# RELAYS.net
KiCad netlist of a schematic drawn in Altium Designer
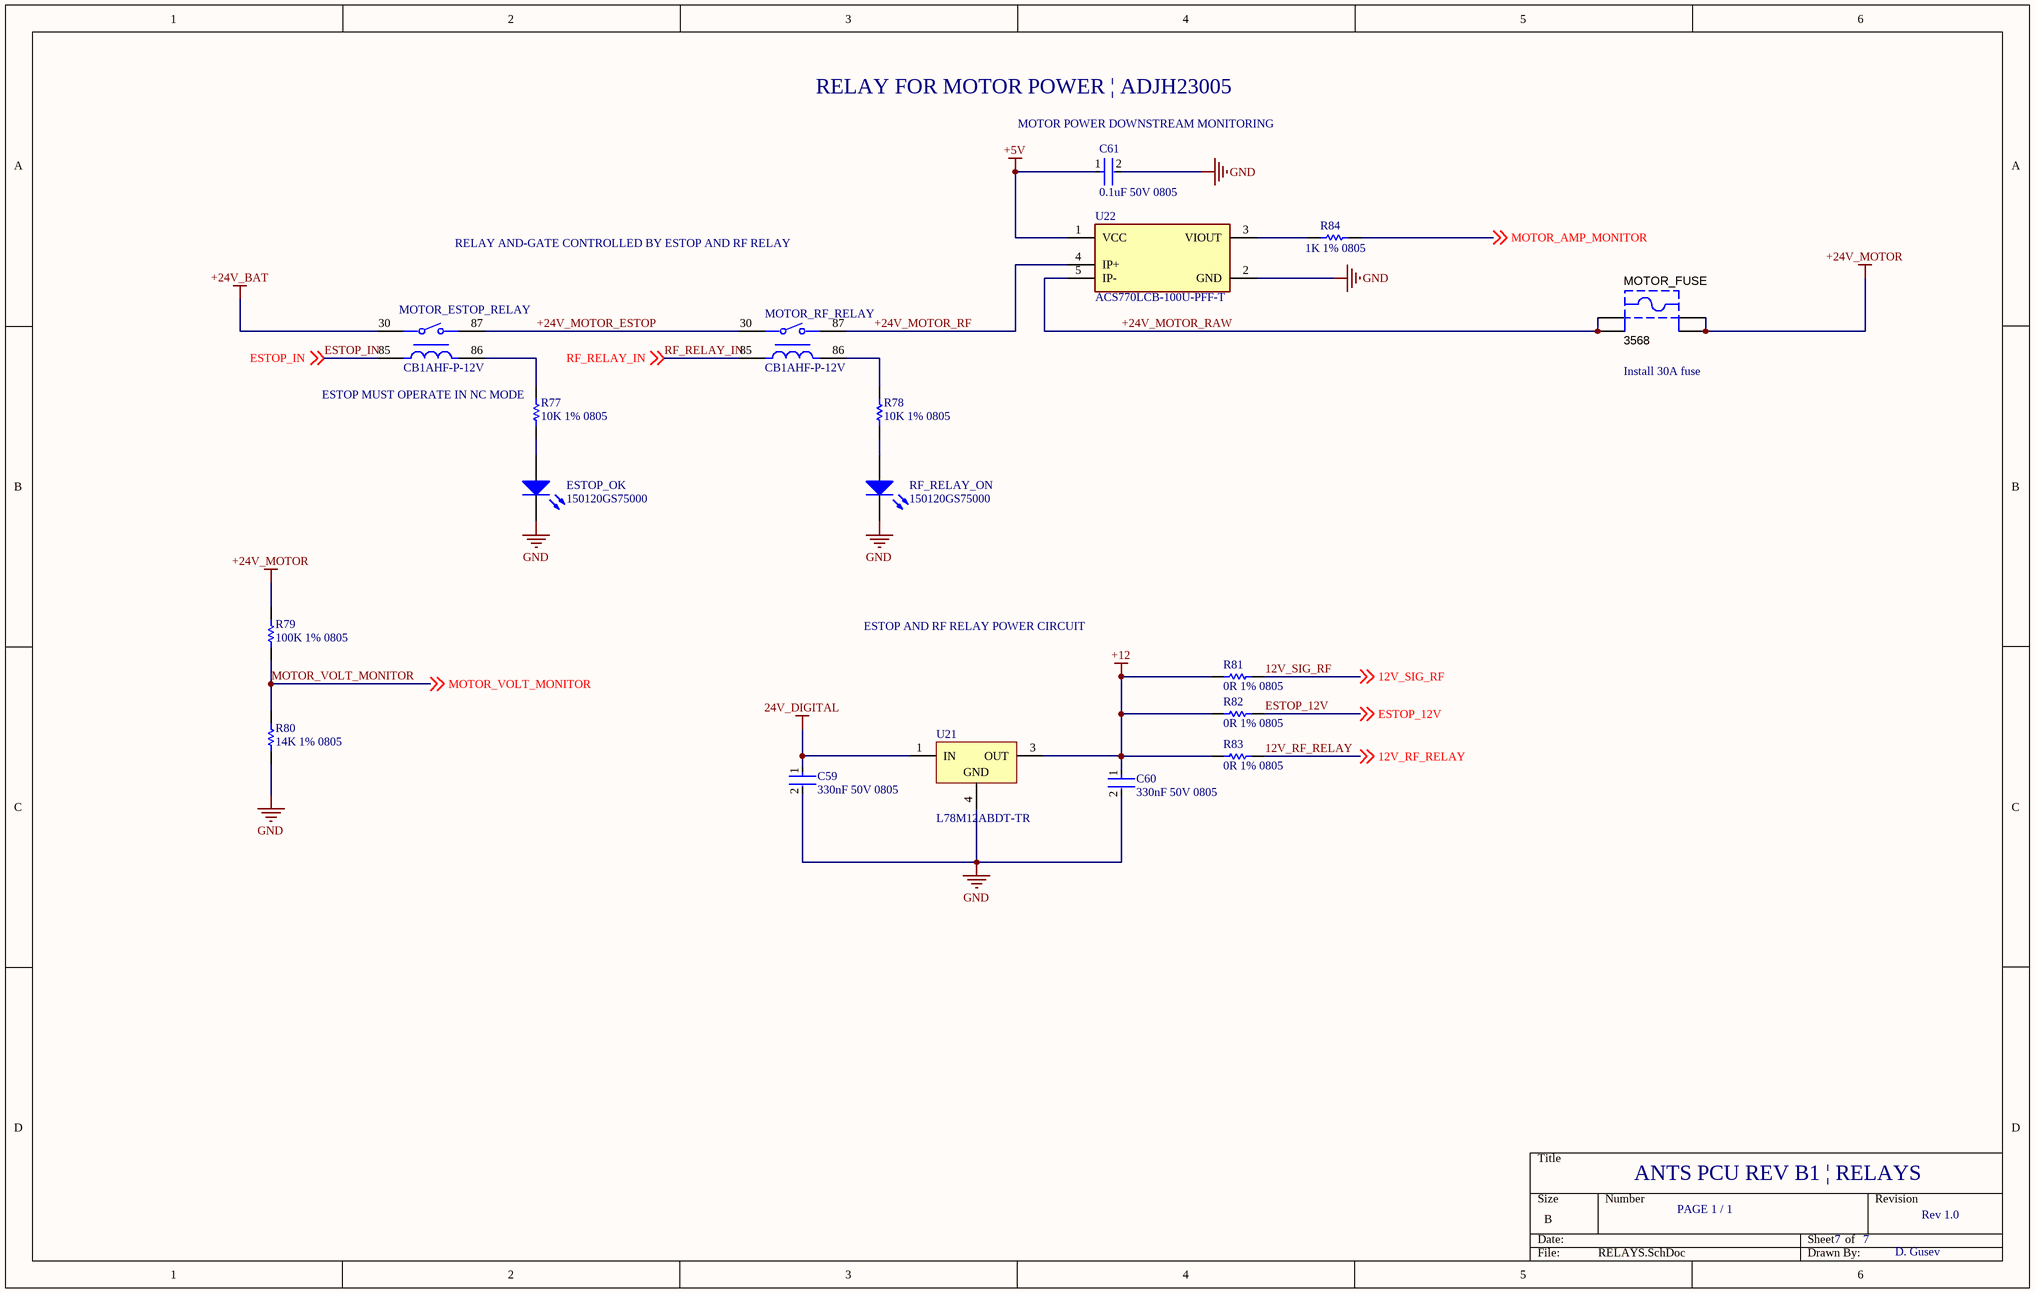
[diagram p0: RELAYS.SchDoc]

(export (version "E")
  (design (tool "Eeschema 10.0.6"))
  (components
    (comp (ref "C59")
      (value "330nF 50V 0805")
      (footprint "FP-C0805C-DN-MFG")
      (description "CAP CER 0.33UF 50V X7R 0805")
      (fields
        (field (name "MANUFACTURER PART NUMBER") "C0805C334K5RACTU")
        (field (name "MANUFACTURER") "KEMET")
      )
      (libsource (lib "Altium Content Vault") (part "b4654b650e69147ec39a6b967a45e02"))
    )
    (comp (ref "C60")
      (value "330nF 50V 0805")
      (footprint "FP-C0805C-DN-MFG")
      (description "CAP CER 0.33UF 50V X7R 0805")
      (fields
        (field (name "MANUFACTURER PART NUMBER") "C0805C334K5RACTU")
        (field (name "MANUFACTURER") "KEMET")
      )
      (libsource (lib "Altium Content Vault") (part "b4654b650e69147ec39a6b967a45e02"))
    )
    (comp (ref "C61")
      (value "0.1uF 50V 0805")
      (footprint "FP-C0805C-DN-MFG")
      (description "CAP CER 0.1UF 50V X7R 0805")
      (fields
        (field (name "MANUFACTURER PART NUMBER") "C0805C104K5RACTU")
        (field (name "MANUFACTURER") "KEMET")
      )
      (libsource (lib "Altium Content Vault") (part "b4654b650e69147ec39a6b967a45e02"))
    )
    (comp (ref "ESTOP_OK")
      (value "150120GS75000")
      (footprint "1206_A")
      (description "SMD mono-color Chip LED, WL-SMCW, Green")
      (fields (field (name "MANUFACTURER") "Wuerth Elektronik"))
      (libsource (lib "Altium Content Vault") (part "WE-LED_K1A2-2"))
    )
    (comp (ref "MOTOR_ESTOP_RELAY")
      (value "CB1AHF-P-12V")
      (footprint "FP-CB1AHF-P-12V-MFG")
      (description "RELAY AUTOMOTIVE SPST 70A 12V")
      (libsource (lib "Altium Content Vault") (part "118a8ddf33a3f36f50d1a42db1624c5"))
    )
    (comp (ref "MOTOR_FUSE")
      (value "3568")
      (footprint "KSTN-3568_V")
      (description "Fuse Holder, 20 A, 500 V, -50 to 145 degC, 4-Pin THD, RoHS")
      (fields (field (name "MANUFACTURER") "Keystone"))
      (libsource (lib "Altium Content Vault") (part "FUSE_HOLDER-4"))
    )
    (comp (ref "MOTOR_RF_RELAY")
      (value "CB1AHF-P-12V")
      (footprint "FP-CB1AHF-P-12V-MFG")
      (description "RELAY AUTOMOTIVE SPST 70A 12V")
      (libsource (lib "Altium Content Vault") (part "118a8ddf33a3f36f50d1a42db1624c5"))
    )
    (comp (ref "R77")
      (value "10K 1% 0805")
      (footprint "RESC2013X60X35NL10T20")
      (description "Chip Resistor, 10 KOhm, +/- 1%, 0.125 W, -55 to 155 degC, 0805 (2012 Metric), RoHS, Tape and Reel")
      (fields (field (name "MANUFACTURER") "Yageo"))
      (libsource (lib "Altium Content Vault") (part "RES-2"))
    )
    (comp (ref "R78")
      (value "10K 1% 0805")
      (footprint "RESC2013X60X35NL10T20")
      (description "Chip Resistor, 10 KOhm, +/- 1%, 0.125 W, -55 to 155 degC, 0805 (2012 Metric), RoHS, Tape and Reel")
      (fields (field (name "MANUFACTURER") "Yageo"))
      (libsource (lib "Altium Content Vault") (part "RES-2"))
    )
    (comp (ref "R79")
      (value "100K 1% 0805")
      (footprint "RESC2013X60X35ML10T20")
      (description "Chip Resistor, 100 KOhm, +/- 1%, 0.125 W, -55 to 155 degC, 0805 (2012 Metric), RoHS, Tape and Reel")
      (fields (field (name "MANUFACTURER") "Yageo") (field (name "TOLERANCE") "1%"))
      (libsource (lib "Altium Content Vault") (part "RES-2"))
    )
    (comp (ref "R80")
      (value "14K 1% 0805")
      (footprint "RESC2013X60X35LL10T20")
      (fields (field (name "PART NUMBER") "RC0805FR-0714KL") (field (name "MANUFACTURER") "Yageo"))
      (libsource (lib "Altium Content Vault") (part "RES"))
    )
    (comp (ref "R81")
      (value "0R 1% 0805")
      (footprint "RESC2013X60X35LL10T20")
      (description "Chip Resistor, 1 Ohm, +/- 1%, 125 mW, -55 to 155 degC, 0805 (2012 Metric), RoHS, Tape and Reel")
      (fields (field (name "MANUFACTURER") "Yageo"))
      (libsource (lib "Altium Content Vault") (part "RES-2"))
    )
    (comp (ref "R82")
      (value "0R 1% 0805")
      (footprint "RESC2013X60X35LL10T20")
      (description "Chip Resistor, 1 Ohm, +/- 1%, 125 mW, -55 to 155 degC, 0805 (2012 Metric), RoHS, Tape and Reel")
      (fields (field (name "MANUFACTURER") "Yageo"))
      (libsource (lib "Altium Content Vault") (part "RES-2"))
    )
    (comp (ref "R83")
      (value "0R 1% 0805")
      (footprint "RESC2013X60X35LL10T20")
      (description "Chip Resistor, 1 Ohm, +/- 1%, 125 mW, -55 to 155 degC, 0805 (2012 Metric), RoHS, Tape and Reel")
      (fields (field (name "MANUFACTURER") "Yageo"))
      (libsource (lib "Altium Content Vault") (part "RES-2"))
    )
    (comp (ref "R84")
      (value "1K 1% 0805")
      (footprint "RESC2013X60X35ML10T20")
      (description "Chip Resistor, 1 KOhm, +/- 1%, 125 mW, -55 to 155 degC, 0805 (2012 Metric), RoHS, Tape and Reel")
      (fields (field (name "TOLERANCE") "1%") (field (name "MANUFACTURER") "Yageo"))
      (libsource (lib "Altium Content Vault") (part "RES-2"))
    )
    (comp (ref "RF_RELAY_ON")
      (value "150120GS75000")
      (footprint "1206_A")
      (description "SMD mono-color Chip LED, WL-SMCW, Green")
      (fields (field (name "MANUFACTURER") "Wuerth Elektronik"))
      (libsource (lib "Altium Content Vault") (part "WE-LED_K1A2-2"))
    )
    (comp (ref "U21")
      (value "L78M12ABDT-TR")
      (footprint "TO-252_M")
      (description "Precision 500mA Regulator, 12V, 3-Pin DPAK, Tape and Reel")
      (libsource (lib "Altium Content Vault") (part "PM-REG-L4940-SOT3"))
    )
    (comp (ref "U22")
      (value "ACS770LCB-100U-PFF-T")
      (footprint "ACS770LCB-100U-PFF-T")
      (description "SENSOR CURRENT HALL 100A DC")
      (libsource (lib "ANTS-PCU-B1") (part "ACS770LCB-100U-PFF-T"))
    )
  )
  (nets
    (net (code "1") (name "+5V") (class "Default")
      (node (ref "C61") (pin "1") (pinfunction "1_1") (pintype "passive"))
      (node (ref "U22") (pin "1") (pinfunction "VCC_1") (pintype "power_in"))
    )
    (net (code "2") (name "+12") (class "Default")
      (node (ref "C60") (pin "1") (pinfunction "1_1") (pintype "passive"))
      (node (ref "R81") (pin "1") (pinfunction "1_1") (pintype "passive"))
      (node (ref "R82") (pin "1") (pinfunction "1_1") (pintype "passive"))
      (node (ref "R83") (pin "1") (pinfunction "1_1") (pintype "passive"))
      (node (ref "U21") (pin "3") (pinfunction "OUT_3") (pintype "power_in"))
    )
    (net (code "3") (name "+24V_BAT") (class "Default")
      (node (ref "MOTOR_ESTOP_RELAY") (pin "30") (pinfunction "30_30") (pintype "passive"))
    )
    (net (code "4") (name "+24V_MOTOR") (class "Default")
      (node (ref "MOTOR_FUSE") (pin "3") (pinfunction "3_3") (pintype "passive"))
      (node (ref "MOTOR_FUSE") (pin "4") (pinfunction "4_4") (pintype "passive"))
      (node (ref "R79") (pin "2") (pinfunction "2_2") (pintype "passive"))
    )
    (net (code "5") (name "/+24V_MOTOR_ESTOP") (class "Default")
      (node (ref "MOTOR_ESTOP_RELAY") (pin "87") (pinfunction "87_87") (pintype "passive"))
      (node (ref "MOTOR_RF_RELAY") (pin "30") (pinfunction "30_30") (pintype "passive"))
    )
    (net (code "6") (name "/+24V_MOTOR_RAW") (class "Default")
      (node (ref "MOTOR_FUSE") (pin "1") (pinfunction "1_1") (pintype "passive"))
      (node (ref "MOTOR_FUSE") (pin "2") (pinfunction "2_2") (pintype "passive"))
      (node (ref "U22") (pin "5") (pinfunction "IP-_5") (pintype "passive"))
    )
    (net (code "7") (name "/+24V_MOTOR_RF") (class "Default")
      (node (ref "MOTOR_RF_RELAY") (pin "87") (pinfunction "87_87") (pintype "passive"))
      (node (ref "U22") (pin "4") (pinfunction "IP+_4") (pintype "passive"))
    )
    (net (code "8") (name "12V_RF_RELAY") (class "Default")
      (node (ref "R83") (pin "2") (pinfunction "2_2") (pintype "passive"))
    )
    (net (code "9") (name "12V_SIG_RF") (class "Default")
      (node (ref "R81") (pin "2") (pinfunction "2_2") (pintype "passive"))
    )
    (net (code "10") (name "24V_DIGITAL") (class "Default")
      (node (ref "C59") (pin "1") (pinfunction "1_1") (pintype "passive"))
      (node (ref "U21") (pin "1") (pinfunction "IN_1") (pintype "power_in"))
    )
    (net (code "11") (name "ESTOP_12V") (class "Default")
      (node (ref "R82") (pin "2") (pinfunction "2_2") (pintype "passive"))
    )
    (net (code "12") (name "ESTOP_IN") (class "Default")
      (node (ref "MOTOR_ESTOP_RELAY") (pin "85") (pinfunction "85_85") (pintype "passive"))
    )
    (net (code "13") (name "GND") (class "Default")
      (node (ref "C59") (pin "2") (pinfunction "2_2") (pintype "passive"))
      (node (ref "C60") (pin "2") (pinfunction "2_2") (pintype "passive"))
      (node (ref "C61") (pin "2") (pinfunction "2_2") (pintype "passive"))
      (node (ref "ESTOP_OK") (pin "1") (pinfunction "K_1") (pintype "passive"))
      (node (ref "R80") (pin "1") (pinfunction "1_1") (pintype "passive"))
      (node (ref "RF_RELAY_ON") (pin "1") (pinfunction "K_1") (pintype "passive"))
      (node (ref "U21") (pin "4") (pinfunction "GND_4") (pintype "power_in"))
      (node (ref "U22") (pin "2") (pinfunction "GND_2") (pintype "power_in"))
    )
    (net (code "14") (name "MOTOR_AMP_MONITOR") (class "Default")
      (node (ref "R84") (pin "2") (pinfunction "2_2") (pintype "passive"))
    )
    (net (code "15") (name "MOTOR_VOLT_MONITOR") (class "Default")
      (node (ref "R79") (pin "1") (pinfunction "1_1") (pintype "passive"))
      (node (ref "R80") (pin "2") (pinfunction "2_2") (pintype "passive"))
    )
    (net (code "16") (name "Net-(ESTOP_OK-A)") (class "Default")
      (node (ref "ESTOP_OK") (pin "2") (pinfunction "A_2") (pintype "passive"))
      (node (ref "R77") (pin "1") (pinfunction "1_1") (pintype "passive"))
    )
    (net (code "17") (name "Net-(MOTOR_ESTOP_RELAY-Pad86)") (class "Default")
      (node (ref "MOTOR_ESTOP_RELAY") (pin "86") (pinfunction "86_86") (pintype "passive"))
      (node (ref "R77") (pin "2") (pinfunction "2_2") (pintype "passive"))
    )
    (net (code "18") (name "Net-(MOTOR_RF_RELAY-Pad86)") (class "Default")
      (node (ref "MOTOR_RF_RELAY") (pin "86") (pinfunction "86_86") (pintype "passive"))
      (node (ref "R78") (pin "2") (pinfunction "2_2") (pintype "passive"))
    )
    (net (code "19") (name "Net-(RF_RELAY_ON-A)") (class "Default")
      (node (ref "R78") (pin "1") (pinfunction "1_1") (pintype "passive"))
      (node (ref "RF_RELAY_ON") (pin "2") (pinfunction "A_2") (pintype "passive"))
    )
    (net (code "20") (name "Net-(U22-VIOUT)") (class "Default")
      (node (ref "R84") (pin "1") (pinfunction "1_1") (pintype "passive"))
      (node (ref "U22") (pin "3") (pinfunction "VIOUT_3") (pintype "passive"))
    )
    (net (code "21") (name "RF_RELAY_IN") (class "Default")
      (node (ref "MOTOR_RF_RELAY") (pin "85") (pinfunction "85_85") (pintype "passive"))
    )
  )
)
